# SAM9X75_PWR.net
KiCad netlist of a schematic drawn in Altium Designer
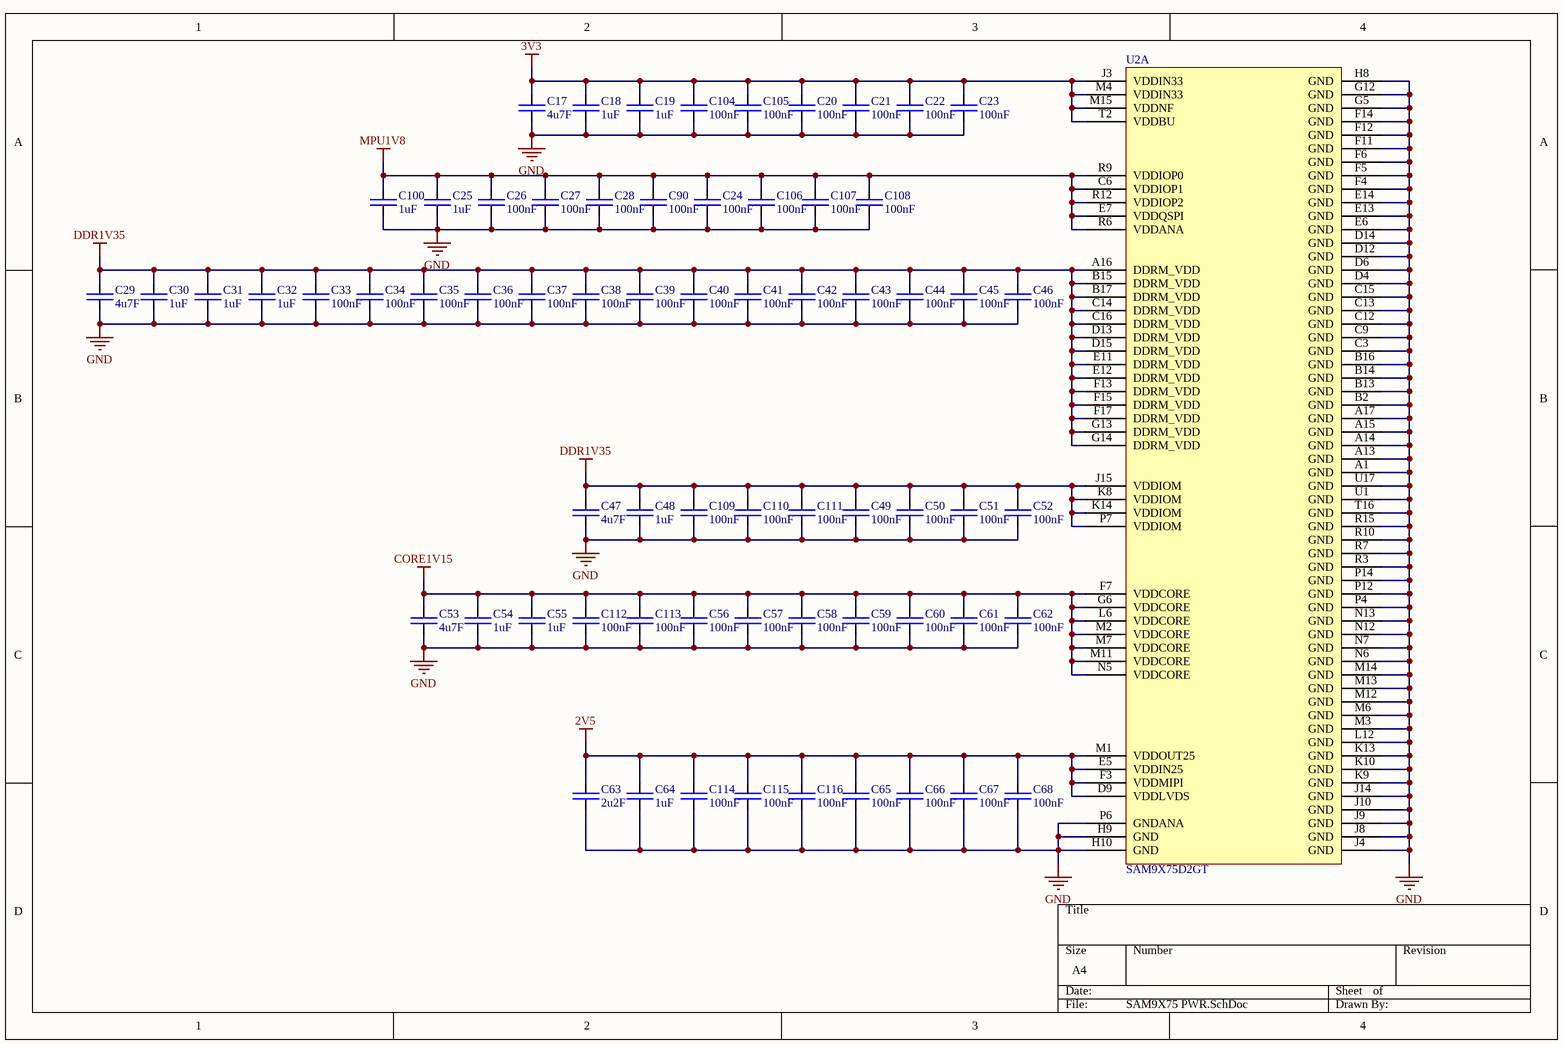
[diagram p0: SAM9X75 PWR.SchDoc]

(export (version "E")
  (design (tool "Eeschema 10.0.6"))
  (components
    (comp (ref "C17")
      (value "4u7F")
      (footprint "CAP-0805")
      (description "Capacitor chip unpolarized. 0805")
      (libsource (lib "Master") (part "CAP-0805"))
    )
    (comp (ref "C18")
      (value "1uF")
      (footprint "CAP-0805")
      (description "Capacitor chip unpolarized. 0805")
      (libsource (lib "Master") (part "CAP-0805"))
    )
    (comp (ref "C19")
      (value "1uF")
      (footprint "CAP-0805")
      (description "Capacitor chip unpolarized. 0805")
      (libsource (lib "Master") (part "CAP-0805"))
    )
    (comp (ref "C20")
      (value "100nF")
      (footprint "CAP-0201")
      (description "Capacitor chip upolarized. 0201")
      (libsource (lib "Master") (part "CAP-0201"))
    )
    (comp (ref "C21")
      (value "100nF")
      (footprint "CAP-0201")
      (description "Capacitor chip upolarized. 0201")
      (libsource (lib "Master") (part "CAP-0201"))
    )
    (comp (ref "C22")
      (value "100nF")
      (footprint "CAP-0201")
      (description "Capacitor chip upolarized. 0201")
      (libsource (lib "Master") (part "CAP-0201"))
    )
    (comp (ref "C23")
      (value "100nF")
      (footprint "CAP-0201")
      (description "Capacitor chip upolarized. 0201")
      (libsource (lib "Master") (part "CAP-0201"))
    )
    (comp (ref "C24")
      (value "100nF")
      (footprint "CAP-0201")
      (description "Capacitor chip upolarized. 0201")
      (libsource (lib "Master") (part "CAP-0201"))
    )
    (comp (ref "C25")
      (value "1uF")
      (footprint "CAP-0805")
      (description "Capacitor chip unpolarized. 0805")
      (libsource (lib "Master") (part "CAP-0805"))
    )
    (comp (ref "C26")
      (value "100nF")
      (footprint "CAP-0201")
      (description "Capacitor chip upolarized. 0201")
      (libsource (lib "Master") (part "CAP-0201"))
    )
    (comp (ref "C27")
      (value "100nF")
      (footprint "CAP-0201")
      (description "Capacitor chip upolarized. 0201")
      (libsource (lib "Master") (part "CAP-0201"))
    )
    (comp (ref "C28")
      (value "100nF")
      (footprint "CAP-0201")
      (description "Capacitor chip upolarized. 0201")
      (libsource (lib "Master") (part "CAP-0201"))
    )
    (comp (ref "C29")
      (value "4u7F")
      (footprint "CAP-0805")
      (description "Capacitor chip unpolarized. 0805")
      (libsource (lib "Master") (part "CAP-0805"))
    )
    (comp (ref "C30")
      (value "1uF")
      (footprint "CAP-0805")
      (description "Capacitor chip unpolarized. 0805")
      (libsource (lib "Master") (part "CAP-0805"))
    )
    (comp (ref "C31")
      (value "1uF")
      (footprint "CAP-0805")
      (description "Capacitor chip unpolarized. 0805")
      (libsource (lib "Master") (part "CAP-0805"))
    )
    (comp (ref "C32")
      (value "1uF")
      (footprint "CAP-0805")
      (description "Capacitor chip unpolarized. 0805")
      (libsource (lib "Master") (part "CAP-0805"))
    )
    (comp (ref "C33")
      (value "100nF")
      (footprint "CAP-0201")
      (description "Capacitor chip upolarized. 0201")
      (libsource (lib "Master") (part "CAP-0201"))
    )
    (comp (ref "C34")
      (value "100nF")
      (footprint "CAP-0201")
      (description "Capacitor chip upolarized. 0201")
      (libsource (lib "Master") (part "CAP-0201"))
    )
    (comp (ref "C35")
      (value "100nF")
      (footprint "CAP-0201")
      (description "Capacitor chip upolarized. 0201")
      (libsource (lib "Master") (part "CAP-0201"))
    )
    (comp (ref "C36")
      (value "100nF")
      (footprint "CAP-0201")
      (description "Capacitor chip upolarized. 0201")
      (libsource (lib "Master") (part "CAP-0201"))
    )
    (comp (ref "C37")
      (value "100nF")
      (footprint "CAP-0201")
      (description "Capacitor chip upolarized. 0201")
      (libsource (lib "Master") (part "CAP-0201"))
    )
    (comp (ref "C38")
      (value "100nF")
      (footprint "CAP-0201")
      (description "Capacitor chip upolarized. 0201")
      (libsource (lib "Master") (part "CAP-0201"))
    )
    (comp (ref "C39")
      (value "100nF")
      (footprint "CAP-0201")
      (description "Capacitor chip upolarized. 0201")
      (libsource (lib "Master") (part "CAP-0201"))
    )
    (comp (ref "C40")
      (value "100nF")
      (footprint "CAP-0201")
      (description "Capacitor chip upolarized. 0201")
      (libsource (lib "Master") (part "CAP-0201"))
    )
    (comp (ref "C41")
      (value "100nF")
      (footprint "CAP-0201")
      (description "Capacitor chip upolarized. 0201")
      (libsource (lib "Master") (part "CAP-0201"))
    )
    (comp (ref "C42")
      (value "100nF")
      (footprint "CAP-0201")
      (description "Capacitor chip upolarized. 0201")
      (libsource (lib "Master") (part "CAP-0201"))
    )
    (comp (ref "C43")
      (value "100nF")
      (footprint "CAP-0201")
      (description "Capacitor chip upolarized. 0201")
      (libsource (lib "Master") (part "CAP-0201"))
    )
    (comp (ref "C44")
      (value "100nF")
      (footprint "CAP-0201")
      (description "Capacitor chip upolarized. 0201")
      (libsource (lib "Master") (part "CAP-0201"))
    )
    (comp (ref "C45")
      (value "100nF")
      (footprint "CAP-0201")
      (description "Capacitor chip upolarized. 0201")
      (libsource (lib "Master") (part "CAP-0201"))
    )
    (comp (ref "C46")
      (value "100nF")
      (footprint "CAP-0201")
      (description "Capacitor chip upolarized. 0201")
      (libsource (lib "Master") (part "CAP-0201"))
    )
    (comp (ref "C47")
      (value "4u7F")
      (footprint "CAP-0805")
      (description "Capacitor chip unpolarized. 0805")
      (libsource (lib "Master") (part "CAP-0805"))
    )
    (comp (ref "C48")
      (value "1uF")
      (footprint "CAP-0805")
      (description "Capacitor chip unpolarized. 0805")
      (libsource (lib "Master") (part "CAP-0805"))
    )
    (comp (ref "C49")
      (value "100nF")
      (footprint "CAP-0201")
      (description "Capacitor chip upolarized. 0201")
      (libsource (lib "Master") (part "CAP-0201"))
    )
    (comp (ref "C50")
      (value "100nF")
      (footprint "CAP-0201")
      (description "Capacitor chip upolarized. 0201")
      (libsource (lib "Master") (part "CAP-0201"))
    )
    (comp (ref "C51")
      (value "100nF")
      (footprint "CAP-0201")
      (description "Capacitor chip upolarized. 0201")
      (libsource (lib "Master") (part "CAP-0201"))
    )
    (comp (ref "C52")
      (value "100nF")
      (footprint "CAP-0201")
      (description "Capacitor chip upolarized. 0201")
      (libsource (lib "Master") (part "CAP-0201"))
    )
    (comp (ref "C53")
      (value "4u7F")
      (footprint "CAP-0805")
      (description "Capacitor chip unpolarized. 0805")
      (libsource (lib "Master") (part "CAP-0805"))
    )
    (comp (ref "C54")
      (value "1uF")
      (footprint "CAP-0805")
      (description "Capacitor chip unpolarized. 0805")
      (libsource (lib "Master") (part "CAP-0805"))
    )
    (comp (ref "C55")
      (value "1uF")
      (footprint "CAP-0805")
      (description "Capacitor chip unpolarized. 0805")
      (libsource (lib "Master") (part "CAP-0805"))
    )
    (comp (ref "C56")
      (value "100nF")
      (footprint "CAP-0201")
      (description "Capacitor chip upolarized. 0201")
      (libsource (lib "Master") (part "CAP-0201"))
    )
    (comp (ref "C57")
      (value "100nF")
      (footprint "CAP-0201")
      (description "Capacitor chip upolarized. 0201")
      (libsource (lib "Master") (part "CAP-0201"))
    )
    (comp (ref "C58")
      (value "100nF")
      (footprint "CAP-0201")
      (description "Capacitor chip upolarized. 0201")
      (libsource (lib "Master") (part "CAP-0201"))
    )
    (comp (ref "C59")
      (value "100nF")
      (footprint "CAP-0201")
      (description "Capacitor chip upolarized. 0201")
      (libsource (lib "Master") (part "CAP-0201"))
    )
    (comp (ref "C60")
      (value "100nF")
      (footprint "CAP-0201")
      (description "Capacitor chip upolarized. 0201")
      (libsource (lib "Master") (part "CAP-0201"))
    )
    (comp (ref "C61")
      (value "100nF")
      (footprint "CAP-0201")
      (description "Capacitor chip upolarized. 0201")
      (libsource (lib "Master") (part "CAP-0201"))
    )
    (comp (ref "C62")
      (value "100nF")
      (footprint "CAP-0201")
      (description "Capacitor chip upolarized. 0201")
      (libsource (lib "Master") (part "CAP-0201"))
    )
    (comp (ref "C63")
      (value "2u2F")
      (footprint "CAP-0805")
      (description "Capacitor chip unpolarized. 0805")
      (libsource (lib "Master") (part "CAP-0805"))
    )
    (comp (ref "C64")
      (value "1uF")
      (footprint "CAP-0805")
      (description "Capacitor chip unpolarized. 0805")
      (libsource (lib "Master") (part "CAP-0805"))
    )
    (comp (ref "C65")
      (value "100nF")
      (footprint "CAP-0201")
      (description "Capacitor chip upolarized. 0201")
      (libsource (lib "Master") (part "CAP-0201"))
    )
    (comp (ref "C66")
      (value "100nF")
      (footprint "CAP-0201")
      (description "Capacitor chip upolarized. 0201")
      (libsource (lib "Master") (part "CAP-0201"))
    )
    (comp (ref "C67")
      (value "100nF")
      (footprint "CAP-0201")
      (description "Capacitor chip upolarized. 0201")
      (libsource (lib "Master") (part "CAP-0201"))
    )
    (comp (ref "C68")
      (value "100nF")
      (footprint "CAP-0201")
      (description "Capacitor chip upolarized. 0201")
      (libsource (lib "Master") (part "CAP-0201"))
    )
    (comp (ref "C90")
      (value "100nF")
      (footprint "CAP-0201")
      (description "Capacitor chip upolarized. 0201")
      (libsource (lib "Master") (part "CAP-0201"))
    )
    (comp (ref "C100")
      (value "1uF")
      (footprint "CAP-0805")
      (description "Capacitor chip unpolarized. 0805")
      (libsource (lib "Master") (part "CAP-0805"))
    )
    (comp (ref "C104")
      (value "100nF")
      (footprint "CAP-0201")
      (description "Capacitor chip upolarized. 0201")
      (libsource (lib "Master") (part "CAP-0201"))
    )
    (comp (ref "C105")
      (value "100nF")
      (footprint "CAP-0201")
      (description "Capacitor chip upolarized. 0201")
      (libsource (lib "Master") (part "CAP-0201"))
    )
    (comp (ref "C106")
      (value "100nF")
      (footprint "CAP-0201")
      (description "Capacitor chip upolarized. 0201")
      (libsource (lib "Master") (part "CAP-0201"))
    )
    (comp (ref "C107")
      (value "100nF")
      (footprint "CAP-0201")
      (description "Capacitor chip upolarized. 0201")
      (libsource (lib "Master") (part "CAP-0201"))
    )
    (comp (ref "C108")
      (value "100nF")
      (footprint "CAP-0201")
      (description "Capacitor chip upolarized. 0201")
      (libsource (lib "Master") (part "CAP-0201"))
    )
    (comp (ref "C109")
      (value "100nF")
      (footprint "CAP-0201")
      (description "Capacitor chip upolarized. 0201")
      (libsource (lib "Master") (part "CAP-0201"))
    )
    (comp (ref "C110")
      (value "100nF")
      (footprint "CAP-0201")
      (description "Capacitor chip upolarized. 0201")
      (libsource (lib "Master") (part "CAP-0201"))
    )
    (comp (ref "C111")
      (value "100nF")
      (footprint "CAP-0201")
      (description "Capacitor chip upolarized. 0201")
      (libsource (lib "Master") (part "CAP-0201"))
    )
    (comp (ref "C112")
      (value "100nF")
      (footprint "CAP-0201")
      (description "Capacitor chip upolarized. 0201")
      (libsource (lib "Master") (part "CAP-0201"))
    )
    (comp (ref "C113")
      (value "100nF")
      (footprint "CAP-0201")
      (description "Capacitor chip upolarized. 0201")
      (libsource (lib "Master") (part "CAP-0201"))
    )
    (comp (ref "C114")
      (value "100nF")
      (footprint "CAP-0201")
      (description "Capacitor chip upolarized. 0201")
      (libsource (lib "Master") (part "CAP-0201"))
    )
    (comp (ref "C115")
      (value "100nF")
      (footprint "CAP-0201")
      (description "Capacitor chip upolarized. 0201")
      (libsource (lib "Master") (part "CAP-0201"))
    )
    (comp (ref "C116")
      (value "100nF")
      (footprint "CAP-0201")
      (description "Capacitor chip upolarized. 0201")
      (libsource (lib "Master") (part "CAP-0201"))
    )
    (comp (ref "U2")
      (value "SAM9X75D2GT")
      (footprint "SAM9X75D")
      (description "ARM9 SiP 2GBit Internal DDR3L")
      (libsource (lib "Master") (part "SAM9X75D2GT"))
    )
  )
  (nets
    (net (code "1") (name "2V5") (class "Default")
      (node (ref "C114") (pin "2") (pintype "passive"))
      (node (ref "C115") (pin "2") (pintype "passive"))
      (node (ref "C116") (pin "2") (pintype "passive"))
      (node (ref "C63") (pin "2") (pintype "passive"))
      (node (ref "C64") (pin "2") (pintype "passive"))
      (node (ref "C65") (pin "2") (pintype "passive"))
      (node (ref "C66") (pin "2") (pintype "passive"))
      (node (ref "C67") (pin "2") (pintype "passive"))
      (node (ref "C68") (pin "2") (pintype "passive"))
      (node (ref "U2") (pin "D9") (pinfunction "VDDLVDS_D9") (pintype "passive"))
      (node (ref "U2") (pin "E5") (pinfunction "VDDIN25_E5") (pintype "passive"))
      (node (ref "U2") (pin "F3") (pinfunction "VDDMIPI_F3") (pintype "passive"))
      (node (ref "U2") (pin "M1") (pinfunction "VDDOUT25_M1") (pintype "passive"))
    )
    (net (code "2") (name "3V3") (class "Default")
      (node (ref "C104") (pin "2") (pintype "passive"))
      (node (ref "C105") (pin "2") (pintype "passive"))
      (node (ref "C17") (pin "2") (pintype "passive"))
      (node (ref "C18") (pin "2") (pintype "passive"))
      (node (ref "C19") (pin "2") (pintype "passive"))
      (node (ref "C20") (pin "2") (pintype "passive"))
      (node (ref "C21") (pin "2") (pintype "passive"))
      (node (ref "C22") (pin "2") (pintype "passive"))
      (node (ref "C23") (pin "2") (pintype "passive"))
      (node (ref "U2") (pin "J3") (pinfunction "VDDIN33_J3") (pintype "passive"))
      (node (ref "U2") (pin "M15") (pinfunction "VDDNF_M15") (pintype "passive"))
      (node (ref "U2") (pin "M4") (pinfunction "VDDIN33_M4") (pintype "passive"))
      (node (ref "U2") (pin "T2") (pinfunction "VDDBU_T2") (pintype "passive"))
    )
    (net (code "3") (name "CORE1V15") (class "Default")
      (node (ref "C112") (pin "2") (pintype "passive"))
      (node (ref "C113") (pin "2") (pintype "passive"))
      (node (ref "C53") (pin "2") (pintype "passive"))
      (node (ref "C54") (pin "2") (pintype "passive"))
      (node (ref "C55") (pin "2") (pintype "passive"))
      (node (ref "C56") (pin "2") (pintype "passive"))
      (node (ref "C57") (pin "2") (pintype "passive"))
      (node (ref "C58") (pin "2") (pintype "passive"))
      (node (ref "C59") (pin "2") (pintype "passive"))
      (node (ref "C60") (pin "2") (pintype "passive"))
      (node (ref "C61") (pin "2") (pintype "passive"))
      (node (ref "C62") (pin "2") (pintype "passive"))
      (node (ref "U2") (pin "F7") (pinfunction "VDDCORE_F7") (pintype "passive"))
      (node (ref "U2") (pin "G6") (pinfunction "VDDCORE_G6") (pintype "passive"))
      (node (ref "U2") (pin "L6") (pinfunction "VDDCORE_L6") (pintype "passive"))
      (node (ref "U2") (pin "M11") (pinfunction "VDDCORE_M11") (pintype "passive"))
      (node (ref "U2") (pin "M2") (pinfunction "VDDCORE_M2") (pintype "passive"))
      (node (ref "U2") (pin "M7") (pinfunction "VDDCORE_M7") (pintype "passive"))
      (node (ref "U2") (pin "N5") (pinfunction "VDDCORE_N5") (pintype "passive"))
    )
    (net (code "4") (name "DDR1V35") (class "Default")
      (node (ref "C109") (pin "2") (pintype "passive"))
      (node (ref "C110") (pin "2") (pintype "passive"))
      (node (ref "C111") (pin "2") (pintype "passive"))
      (node (ref "C29") (pin "2") (pintype "passive"))
      (node (ref "C30") (pin "2") (pintype "passive"))
      (node (ref "C31") (pin "2") (pintype "passive"))
      (node (ref "C32") (pin "2") (pintype "passive"))
      (node (ref "C33") (pin "2") (pintype "passive"))
      (node (ref "C34") (pin "2") (pintype "passive"))
      (node (ref "C35") (pin "2") (pintype "passive"))
      (node (ref "C36") (pin "2") (pintype "passive"))
      (node (ref "C37") (pin "2") (pintype "passive"))
      (node (ref "C38") (pin "2") (pintype "passive"))
      (node (ref "C39") (pin "2") (pintype "passive"))
      (node (ref "C40") (pin "2") (pintype "passive"))
      (node (ref "C41") (pin "2") (pintype "passive"))
      (node (ref "C42") (pin "2") (pintype "passive"))
      (node (ref "C43") (pin "2") (pintype "passive"))
      (node (ref "C44") (pin "2") (pintype "passive"))
      (node (ref "C45") (pin "2") (pintype "passive"))
      (node (ref "C46") (pin "2") (pintype "passive"))
      (node (ref "C47") (pin "2") (pintype "passive"))
      (node (ref "C48") (pin "2") (pintype "passive"))
      (node (ref "C49") (pin "2") (pintype "passive"))
      (node (ref "C50") (pin "2") (pintype "passive"))
      (node (ref "C51") (pin "2") (pintype "passive"))
      (node (ref "C52") (pin "2") (pintype "passive"))
      (node (ref "U2") (pin "A16") (pinfunction "DDRM_VDD_A16") (pintype "passive"))
      (node (ref "U2") (pin "B15") (pinfunction "DDRM_VDD_B15") (pintype "passive"))
      (node (ref "U2") (pin "B17") (pinfunction "DDRM_VDD_B17") (pintype "passive"))
      (node (ref "U2") (pin "C14") (pinfunction "DDRM_VDD_C14") (pintype "passive"))
      (node (ref "U2") (pin "C16") (pinfunction "DDRM_VDD_C16") (pintype "passive"))
      (node (ref "U2") (pin "D13") (pinfunction "DDRM_VDD_D13") (pintype "passive"))
      (node (ref "U2") (pin "D15") (pinfunction "DDRM_VDD_D15") (pintype "passive"))
      (node (ref "U2") (pin "E11") (pinfunction "DDRM_VDD_E11") (pintype "passive"))
      (node (ref "U2") (pin "E12") (pinfunction "DDRM_VDD_E12") (pintype "passive"))
      (node (ref "U2") (pin "F13") (pinfunction "DDRM_VDD_F13") (pintype "passive"))
      (node (ref "U2") (pin "F15") (pinfunction "DDRM_VDD_F15") (pintype "passive"))
      (node (ref "U2") (pin "F17") (pinfunction "DDRM_VDD_F17") (pintype "passive"))
      (node (ref "U2") (pin "G13") (pinfunction "DDRM_VDD_G13") (pintype "passive"))
      (node (ref "U2") (pin "G14") (pinfunction "DDRM_VDD_G14") (pintype "passive"))
      (node (ref "U2") (pin "J15") (pinfunction "VDDIOM_J15") (pintype "passive"))
      (node (ref "U2") (pin "K14") (pinfunction "VDDIOM_K14") (pintype "passive"))
      (node (ref "U2") (pin "K8") (pinfunction "VDDIOM_K8") (pintype "passive"))
      (node (ref "U2") (pin "P7") (pinfunction "VDDIOM_P7") (pintype "passive"))
    )
    (net (code "5") (name "GND") (class "Default")
      (node (ref "C100") (pin "1") (pintype "passive"))
      (node (ref "C104") (pin "1") (pintype "passive"))
      (node (ref "C105") (pin "1") (pintype "passive"))
      (node (ref "C106") (pin "1") (pintype "passive"))
      (node (ref "C107") (pin "1") (pintype "passive"))
      (node (ref "C108") (pin "1") (pintype "passive"))
      (node (ref "C109") (pin "1") (pintype "passive"))
      (node (ref "C110") (pin "1") (pintype "passive"))
      (node (ref "C111") (pin "1") (pintype "passive"))
      (node (ref "C112") (pin "1") (pintype "passive"))
      (node (ref "C113") (pin "1") (pintype "passive"))
      (node (ref "C114") (pin "1") (pintype "passive"))
      (node (ref "C115") (pin "1") (pintype "passive"))
      (node (ref "C116") (pin "1") (pintype "passive"))
      (node (ref "C17") (pin "1") (pintype "passive"))
      (node (ref "C18") (pin "1") (pintype "passive"))
      (node (ref "C19") (pin "1") (pintype "passive"))
      (node (ref "C20") (pin "1") (pintype "passive"))
      (node (ref "C21") (pin "1") (pintype "passive"))
      (node (ref "C22") (pin "1") (pintype "passive"))
      (node (ref "C23") (pin "1") (pintype "passive"))
      (node (ref "C24") (pin "1") (pintype "passive"))
      (node (ref "C25") (pin "1") (pintype "passive"))
      (node (ref "C26") (pin "1") (pintype "passive"))
      (node (ref "C27") (pin "1") (pintype "passive"))
      (node (ref "C28") (pin "1") (pintype "passive"))
      (node (ref "C29") (pin "1") (pintype "passive"))
      (node (ref "C30") (pin "1") (pintype "passive"))
      (node (ref "C31") (pin "1") (pintype "passive"))
      (node (ref "C32") (pin "1") (pintype "passive"))
      (node (ref "C33") (pin "1") (pintype "passive"))
      (node (ref "C34") (pin "1") (pintype "passive"))
      (node (ref "C35") (pin "1") (pintype "passive"))
      (node (ref "C36") (pin "1") (pintype "passive"))
      (node (ref "C37") (pin "1") (pintype "passive"))
      (node (ref "C38") (pin "1") (pintype "passive"))
      (node (ref "C39") (pin "1") (pintype "passive"))
      (node (ref "C40") (pin "1") (pintype "passive"))
      (node (ref "C41") (pin "1") (pintype "passive"))
      (node (ref "C42") (pin "1") (pintype "passive"))
      (node (ref "C43") (pin "1") (pintype "passive"))
      (node (ref "C44") (pin "1") (pintype "passive"))
      (node (ref "C45") (pin "1") (pintype "passive"))
      (node (ref "C46") (pin "1") (pintype "passive"))
      (node (ref "C47") (pin "1") (pintype "passive"))
      (node (ref "C48") (pin "1") (pintype "passive"))
      (node (ref "C49") (pin "1") (pintype "passive"))
      (node (ref "C50") (pin "1") (pintype "passive"))
      (node (ref "C51") (pin "1") (pintype "passive"))
      (node (ref "C52") (pin "1") (pintype "passive"))
      (node (ref "C53") (pin "1") (pintype "passive"))
      (node (ref "C54") (pin "1") (pintype "passive"))
      (node (ref "C55") (pin "1") (pintype "passive"))
      (node (ref "C56") (pin "1") (pintype "passive"))
      (node (ref "C57") (pin "1") (pintype "passive"))
      (node (ref "C58") (pin "1") (pintype "passive"))
      (node (ref "C59") (pin "1") (pintype "passive"))
      (node (ref "C60") (pin "1") (pintype "passive"))
      (node (ref "C61") (pin "1") (pintype "passive"))
      (node (ref "C62") (pin "1") (pintype "passive"))
      (node (ref "C63") (pin "1") (pintype "passive"))
      (node (ref "C64") (pin "1") (pintype "passive"))
      (node (ref "C65") (pin "1") (pintype "passive"))
      (node (ref "C66") (pin "1") (pintype "passive"))
      (node (ref "C67") (pin "1") (pintype "passive"))
      (node (ref "C68") (pin "1") (pintype "passive"))
      (node (ref "C90") (pin "1") (pintype "passive"))
      (node (ref "U2") (pin "A1") (pinfunction "GND_A1") (pintype "passive"))
      (node (ref "U2") (pin "A13") (pinfunction "GND_A13") (pintype "passive"))
      (node (ref "U2") (pin "A14") (pinfunction "GND_A14") (pintype "passive"))
      (node (ref "U2") (pin "A15") (pinfunction "GND_A15") (pintype "passive"))
      (node (ref "U2") (pin "A17") (pinfunction "GND_A17") (pintype "passive"))
      (node (ref "U2") (pin "B13") (pinfunction "GND_B13") (pintype "passive"))
      (node (ref "U2") (pin "B14") (pinfunction "GND_B14") (pintype "passive"))
      (node (ref "U2") (pin "B16") (pinfunction "GND_B16") (pintype "passive"))
      (node (ref "U2") (pin "B2") (pinfunction "GND_B2") (pintype "passive"))
      (node (ref "U2") (pin "C12") (pinfunction "GND_C12") (pintype "passive"))
      (node (ref "U2") (pin "C13") (pinfunction "GND_C13") (pintype "passive"))
      (node (ref "U2") (pin "C15") (pinfunction "GND_C15") (pintype "passive"))
      (node (ref "U2") (pin "C3") (pinfunction "GND_C3") (pintype "passive"))
      (node (ref "U2") (pin "C9") (pinfunction "GND_C9") (pintype "passive"))
      (node (ref "U2") (pin "D12") (pinfunction "GND_D12") (pintype "passive"))
      (node (ref "U2") (pin "D14") (pinfunction "GND_D14") (pintype "passive"))
      (node (ref "U2") (pin "D4") (pinfunction "GND_D4") (pintype "passive"))
      (node (ref "U2") (pin "D6") (pinfunction "GND_D6") (pintype "passive"))
      (node (ref "U2") (pin "E13") (pinfunction "GND_E13") (pintype "passive"))
      (node (ref "U2") (pin "E14") (pinfunction "GND_E14") (pintype "passive"))
      (node (ref "U2") (pin "E6") (pinfunction "GND_E6") (pintype "passive"))
      (node (ref "U2") (pin "F11") (pinfunction "GND_F11") (pintype "passive"))
      (node (ref "U2") (pin "F12") (pinfunction "GND_F12") (pintype "passive"))
      (node (ref "U2") (pin "F14") (pinfunction "GND_F14") (pintype "passive"))
      (node (ref "U2") (pin "F4") (pinfunction "GND_F4") (pintype "passive"))
      (node (ref "U2") (pin "F5") (pinfunction "GND_F5") (pintype "passive"))
      (node (ref "U2") (pin "F6") (pinfunction "GND_F6") (pintype "passive"))
      (node (ref "U2") (pin "G12") (pinfunction "GND_G12") (pintype "passive"))
      (node (ref "U2") (pin "G5") (pinfunction "GND_G5") (pintype "passive"))
      (node (ref "U2") (pin "H10") (pinfunction "GND_H10") (pintype "passive"))
      (node (ref "U2") (pin "H8") (pinfunction "GND_H8") (pintype "passive"))
      (node (ref "U2") (pin "H9") (pinfunction "GND_H9") (pintype "passive"))
      (node (ref "U2") (pin "J10") (pinfunction "GND_J10") (pintype "passive"))
      (node (ref "U2") (pin "J14") (pinfunction "GND_J14") (pintype "passive"))
      (node (ref "U2") (pin "J4") (pinfunction "GND_J4") (pintype "passive"))
      (node (ref "U2") (pin "J8") (pinfunction "GND_J8") (pintype "passive"))
      (node (ref "U2") (pin "J9") (pinfunction "GND_J9") (pintype "passive"))
      (node (ref "U2") (pin "K10") (pinfunction "GND_K10") (pintype "passive"))
      (node (ref "U2") (pin "K13") (pinfunction "GND_K13") (pintype "passive"))
      (node (ref "U2") (pin "K9") (pinfunction "GND_K9") (pintype "passive"))
      (node (ref "U2") (pin "L12") (pinfunction "GND_L12") (pintype "passive"))
      (node (ref "U2") (pin "M12") (pinfunction "GND_M12") (pintype "passive"))
      (node (ref "U2") (pin "M13") (pinfunction "GND_M13") (pintype "passive"))
      (node (ref "U2") (pin "M14") (pinfunction "GND_M14") (pintype "passive"))
      (node (ref "U2") (pin "M3") (pinfunction "GND_M3") (pintype "passive"))
      (node (ref "U2") (pin "M6") (pinfunction "GND_M6") (pintype "passive"))
      (node (ref "U2") (pin "N12") (pinfunction "GND_N12") (pintype "passive"))
      (node (ref "U2") (pin "N13") (pinfunction "GND_N13") (pintype "passive"))
      (node (ref "U2") (pin "N6") (pinfunction "GND_N6") (pintype "passive"))
      (node (ref "U2") (pin "N7") (pinfunction "GND_N7") (pintype "passive"))
      (node (ref "U2") (pin "P12") (pinfunction "GND_P12") (pintype "passive"))
      (node (ref "U2") (pin "P14") (pinfunction "GND_P14") (pintype "passive"))
      (node (ref "U2") (pin "P4") (pinfunction "GND_P4") (pintype "passive"))
      (node (ref "U2") (pin "P6") (pinfunction "GNDANA_P6") (pintype "passive"))
      (node (ref "U2") (pin "R10") (pinfunction "GND_R10") (pintype "passive"))
      (node (ref "U2") (pin "R15") (pinfunction "GND_R15") (pintype "passive"))
      (node (ref "U2") (pin "R3") (pinfunction "GND_R3") (pintype "passive"))
      (node (ref "U2") (pin "R7") (pinfunction "GND_R7") (pintype "passive"))
      (node (ref "U2") (pin "T16") (pinfunction "GND_T16") (pintype "passive"))
      (node (ref "U2") (pin "U1") (pinfunction "GND_U1") (pintype "passive"))
      (node (ref "U2") (pin "U17") (pinfunction "GND_U17") (pintype "passive"))
    )
    (net (code "6") (name "MPU1V8") (class "Default")
      (node (ref "C100") (pin "2") (pintype "passive"))
      (node (ref "C106") (pin "2") (pintype "passive"))
      (node (ref "C107") (pin "2") (pintype "passive"))
      (node (ref "C108") (pin "2") (pintype "passive"))
      (node (ref "C24") (pin "2") (pintype "passive"))
      (node (ref "C25") (pin "2") (pintype "passive"))
      (node (ref "C26") (pin "2") (pintype "passive"))
      (node (ref "C27") (pin "2") (pintype "passive"))
      (node (ref "C28") (pin "2") (pintype "passive"))
      (node (ref "C90") (pin "2") (pintype "passive"))
      (node (ref "U2") (pin "C6") (pinfunction "VDDIOP1_C6") (pintype "passive"))
      (node (ref "U2") (pin "E7") (pinfunction "VDDQSPI_E7") (pintype "passive"))
      (node (ref "U2") (pin "R12") (pinfunction "VDDIOP2_R12") (pintype "passive"))
      (node (ref "U2") (pin "R6") (pinfunction "VDDANA_R6") (pintype "passive"))
      (node (ref "U2") (pin "R9") (pinfunction "VDDIOP0_R9") (pintype "passive"))
    )
  )
)
